# Sheet1.net
KiCad netlist of a schematic drawn in Altium Designer
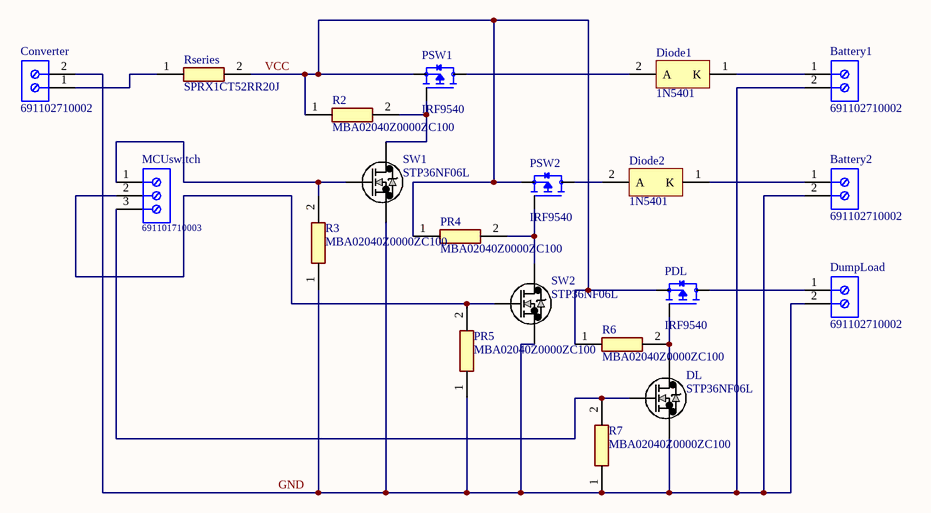
[diagram p0: Sheet1.SchDoc]

(export (version "E")
  (design (tool "Eeschema 10.0.6"))
  (components
    (comp (ref "Battery1")
      (value "691102710002")
      (footprint "691102710002")
      (description "Series 102 - 5.00 mm Horizontal Entry Modular with Pressure Clamp WR-TBL, 2 pin")
      (fields (field (name "MANUFACTURER") "Wurth Elektronik") (field (name "PUBLISHER") "WurthElektronik"))
      (libsource (lib "Altium Content Vault") (part "WE-CN-1P-F-TB2"))
    )
    (comp (ref "Battery2")
      (value "691102710002")
      (footprint "691102710002")
      (description "Series 102 - 5.00 mm Horizontal Entry Modular with Pressure Clamp WR-TBL, 2 pin")
      (fields (field (name "MANUFACTURER") "Wurth Elektronik") (field (name "PUBLISHER") "WurthElektronik"))
      (libsource (lib "Altium Content Vault") (part "WE-CN-1P-F-TB2"))
    )
    (comp (ref "Converter")
      (value "691102710002")
      (footprint "691102710002")
      (description "Series 102 - 5.00 mm Horizontal Entry Modular with Pressure Clamp WR-TBL, 2 pin")
      (fields (field (name "MANUFACTURER") "Wurth Elektronik") (field (name "PUBLISHER") "WurthElektronik"))
      (libsource (lib "Altium Content Vault") (part "WE-CN-1P-F-TB2"))
    )
    (comp (ref "Diode1")
      (value "1N5401")
      (footprint "ONSC-AXIAL_LEAD-2-267-05_V")
      (description "Standard Recovery Rectifier, 2-Pin Axial_Lead, Pb-Free, Bulk Box")
      (fields (field (name "MANUFACTURER") "On Semiconductor"))
      (libsource (lib "Altium Content Vault") (part "ONSC-D-K1A2-2_A"))
    )
    (comp (ref "Diode2")
      (value "1N5401")
      (footprint "ONSC-AXIAL_LEAD-2-267-05_V")
      (description "Standard Recovery Rectifier, 2-Pin Axial_Lead, Pb-Free, Bulk Box")
      (fields (field (name "MANUFACTURER") "On Semiconductor"))
      (libsource (lib "Altium Content Vault") (part "ONSC-D-K1A2-2_A"))
    )
    (comp (ref "DL")
      (value "STP36NF06L")
      (footprint "TO-220_STM")
      (description "No Description Available")
      (fields (field (name "COPYRIGHT") "Copyright (C) 2022 Ultra Librarian. All rights reserved."))
      (libsource (lib "Schlib1") (part "STP36NF06L"))
    )
    (comp (ref "DumpLoad")
      (value "691102710002")
      (footprint "691102710002")
      (description "Series 102 - 5.00 mm Horizontal Entry Modular with Pressure Clamp WR-TBL, 2 pin")
      (fields (field (name "MANUFACTURER") "Wurth Elektronik") (field (name "PUBLISHER") "WurthElektronik"))
      (libsource (lib "Altium Content Vault") (part "WE-CN-1P-F-TB2"))
    )
    (comp (ref "MCUswitch")
      (value "691101710003")
      (footprint "691101710003")
      (description "Series 101 - 5.00 mm Horizontal Entry Modular with Pressure Clamp WR-TBL, 3 pin")
      (fields (field (name "MANUFACTURER") "Wurth Elektronik") (field (name "PUBLISHER") "WurthElektronik"))
      (libsource (lib "Altium Content Vault") (part "WE-CN-1P-F-TB3"))
    )
    (comp (ref "PDL")
      (value "IRF9540")
      (footprint "TO254P1052X465X1989-3")
      (description "P-Channel 100V 19A (Tc) 150W (Tc) Through Hole TO-220AB")
      (fields (field (name "MF") "Vishay Siliconix") (field (name "DIGI-KEY_PART_NUMBER") "IRF9540PBF-ND"))
      (libsource (lib "IRF9540") (part "IRF9540"))
    )
    (comp (ref "PR4")
      (value "MBA02040Z0000ZC100")
      (footprint "SamacSys:RESAD1000W50L360D160")
      (description "Resistor")
      (libsource (lib "") (part "MBA02040Z0000ZC100_1"))
    )
    (comp (ref "PR5")
      (value "MBA02040Z0000ZC100")
      (footprint "SamacSys:RESAD1000W50L360D160")
      (description "Resistor")
      (libsource (lib "*") (part "MBA02040Z0000ZC100"))
    )
    (comp (ref "PSW1")
      (value "IRF9540")
      (footprint "TO254P1052X465X1989-3")
      (description "P-Channel 100V 19A (Tc) 150W (Tc) Through Hole TO-220AB")
      (fields (field (name "MF") "Vishay Siliconix") (field (name "DIGI-KEY_PART_NUMBER") "IRF9540PBF-ND"))
      (libsource (lib "IRF9540") (part "IRF9540"))
    )
    (comp (ref "PSW2")
      (value "IRF9540")
      (footprint "TO254P1052X465X1989-3")
      (description "P-Channel 100V 19A (Tc) 150W (Tc) Through Hole TO-220AB")
      (fields (field (name "MF") "Vishay Siliconix") (field (name "DIGI-KEY_PART_NUMBER") "IRF9540PBF-ND"))
      (libsource (lib "IRF9540") (part "IRF9540"))
    )
    (comp (ref "R2")
      (value "MBA02040Z0000ZC100")
      (footprint "SamacSys:RESAD1000W50L360D160")
      (description "Resistor")
      (libsource (lib "") (part "MBA02040Z0000ZC100_1"))
    )
    (comp (ref "R3")
      (value "MBA02040Z0000ZC100")
      (footprint "SamacSys:RESAD1000W50L360D160")
      (description "Resistor")
      (libsource (lib "*") (part "MBA02040Z0000ZC100"))
    )
    (comp (ref "R6")
      (value "MBA02040Z0000ZC100")
      (footprint "SamacSys:RESAD1000W50L360D160")
      (description "Resistor")
      (libsource (lib "") (part "MBA02040Z0000ZC100_1"))
    )
    (comp (ref "R7")
      (value "MBA02040Z0000ZC100")
      (footprint "SamacSys:RESAD1000W50L360D160")
      (description "Resistor")
      (libsource (lib "*") (part "MBA02040Z0000ZC100"))
    )
    (comp (ref "Rseries")
      (value "SPRX1CT52RR20J")
      (footprint "SamacSys:RESAD2300W80L900D350")
      (description "Resistor")
      (libsource (lib "*") (part "SPRX1CT52RR20J"))
    )
    (comp (ref "SW1")
      (value "STP36NF06L")
      (footprint "TO-220_STM")
      (description "No Description Available")
      (fields (field (name "COPYRIGHT") "Copyright (C) 2022 Ultra Librarian. All rights reserved."))
      (libsource (lib "Schlib1") (part "STP36NF06L"))
    )
    (comp (ref "SW2")
      (value "STP36NF06L")
      (footprint "TO-220_STM")
      (description "No Description Available")
      (fields (field (name "COPYRIGHT") "Copyright (C) 2022 Ultra Librarian. All rights reserved."))
      (libsource (lib "Schlib1") (part "STP36NF06L"))
    )
  )
  (nets
    (net (code "1") (name "/GND") (class "Default")
      (node (ref "Battery1") (pin "2") (pinfunction "2_2") (pintype "passive"))
      (node (ref "Battery2") (pin "2") (pinfunction "2_2") (pintype "passive"))
      (node (ref "Converter") (pin "2") (pinfunction "2_2") (pintype "passive"))
      (node (ref "DL") (pin "3") (pinfunction "3_3") (pintype "passive"))
      (node (ref "DumpLoad") (pin "2") (pinfunction "2_2") (pintype "passive"))
      (node (ref "PR5") (pin "1") (pinfunction "1_1") (pintype "passive"))
      (node (ref "R3") (pin "1") (pinfunction "1_1") (pintype "passive"))
      (node (ref "R7") (pin "1") (pinfunction "1_1") (pintype "passive"))
      (node (ref "SW1") (pin "3") (pinfunction "3_3") (pintype "passive"))
      (node (ref "SW2") (pin "3") (pinfunction "3_3") (pintype "passive"))
    )
    (net (code "2") (name "/VCC") (class "Default")
      (node (ref "PDL") (pin "3") (pinfunction "S_3") (pintype "passive"))
      (node (ref "PR4") (pin "1") (pinfunction "1_1") (pintype "passive"))
      (node (ref "PSW1") (pin "3") (pinfunction "S_3") (pintype "passive"))
      (node (ref "PSW2") (pin "3") (pinfunction "S_3") (pintype "passive"))
      (node (ref "R2") (pin "1") (pinfunction "1_1") (pintype "passive"))
      (node (ref "R6") (pin "1") (pinfunction "1_1") (pintype "passive"))
      (node (ref "Rseries") (pin "2") (pinfunction "2_2") (pintype "passive"))
    )
    (net (code "3") (name "Net-(Converter-Pad1)") (class "Default")
      (node (ref "Converter") (pin "1") (pinfunction "1_1") (pintype "passive"))
      (node (ref "Rseries") (pin "1") (pinfunction "1_1") (pintype "passive"))
    )
    (net (code "4") (name "Net-(DL-Pad1)") (class "Default")
      (node (ref "DL") (pin "1") (pinfunction "1_1") (pintype "passive"))
      (node (ref "MCUswitch") (pin "3") (pinfunction "3_3") (pintype "passive"))
      (node (ref "R7") (pin "2") (pinfunction "2_2") (pintype "passive"))
    )
    (net (code "5") (name "Net-(Diode1-A)") (class "Default")
      (node (ref "Diode1") (pin "2") (pinfunction "A_2") (pintype "passive"))
      (node (ref "PSW1") (pin "2") (pinfunction "D_2") (pintype "passive"))
    )
    (net (code "6") (name "Net-(Diode1-K)") (class "Default")
      (node (ref "Battery1") (pin "1") (pinfunction "1_1") (pintype "passive"))
      (node (ref "Diode1") (pin "1") (pinfunction "K_1") (pintype "passive"))
    )
    (net (code "7") (name "Net-(Diode2-A)") (class "Default")
      (node (ref "Diode2") (pin "2") (pinfunction "A_2") (pintype "passive"))
      (node (ref "PSW2") (pin "2") (pinfunction "D_2") (pintype "passive"))
    )
    (net (code "8") (name "Net-(Diode2-K)") (class "Default")
      (node (ref "Battery2") (pin "1") (pinfunction "1_1") (pintype "passive"))
      (node (ref "Diode2") (pin "1") (pinfunction "K_1") (pintype "passive"))
    )
    (net (code "9") (name "Net-(MCUswitch-Pad1)") (class "Default")
      (node (ref "MCUswitch") (pin "1") (pinfunction "1_1") (pintype "passive"))
      (node (ref "R3") (pin "2") (pinfunction "2_2") (pintype "passive"))
      (node (ref "SW1") (pin "1") (pinfunction "1_1") (pintype "passive"))
    )
    (net (code "10") (name "Net-(MCUswitch-Pad2)") (class "Default")
      (node (ref "MCUswitch") (pin "2") (pinfunction "2_2") (pintype "passive"))
      (node (ref "PR5") (pin "2") (pinfunction "2_2") (pintype "passive"))
      (node (ref "SW2") (pin "1") (pinfunction "1_1") (pintype "passive"))
    )
    (net (code "11") (name "Net-(PDL-D)") (class "Default")
      (node (ref "DumpLoad") (pin "1") (pinfunction "1_1") (pintype "passive"))
      (node (ref "PDL") (pin "2") (pinfunction "D_2") (pintype "passive"))
    )
    (net (code "12") (name "Net-(PDL-G)") (class "Default")
      (node (ref "DL") (pin "2") (pinfunction "2_2") (pintype "passive"))
      (node (ref "PDL") (pin "1") (pinfunction "G_1") (pintype "passive"))
      (node (ref "R6") (pin "2") (pinfunction "2_2") (pintype "passive"))
    )
    (net (code "13") (name "Net-(PSW1-G)") (class "Default")
      (node (ref "PSW1") (pin "1") (pinfunction "G_1") (pintype "passive"))
      (node (ref "R2") (pin "2") (pinfunction "2_2") (pintype "passive"))
      (node (ref "SW1") (pin "2") (pinfunction "2_2") (pintype "passive"))
    )
    (net (code "14") (name "Net-(PSW2-G)") (class "Default")
      (node (ref "PR4") (pin "2") (pinfunction "2_2") (pintype "passive"))
      (node (ref "PSW2") (pin "1") (pinfunction "G_1") (pintype "passive"))
      (node (ref "SW2") (pin "2") (pinfunction "2_2") (pintype "passive"))
    )
  )
)
